# BBB_Cape_template.net
KiCad netlist of a schematic drawn in Altium Designer
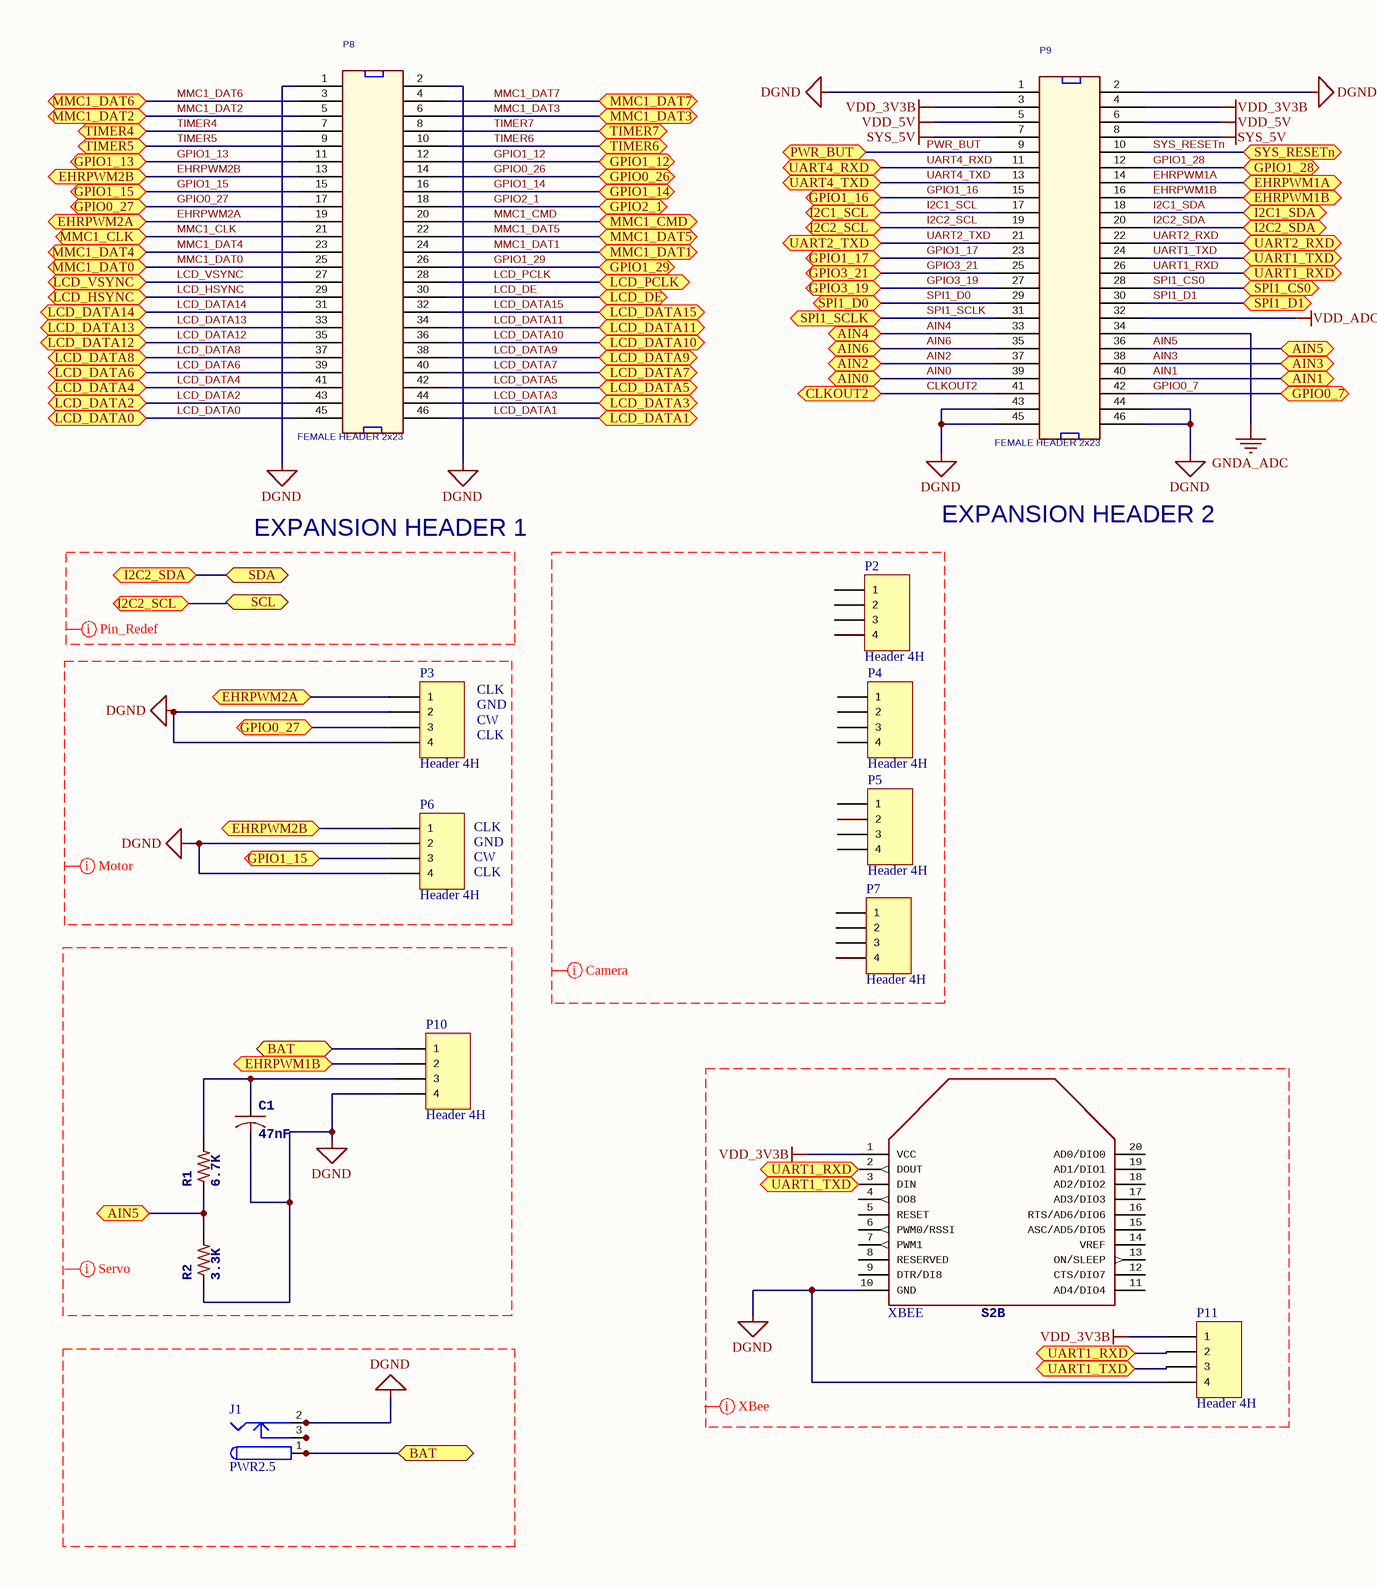
[diagram p0: BBB_Cape_template.SchDoc, left]
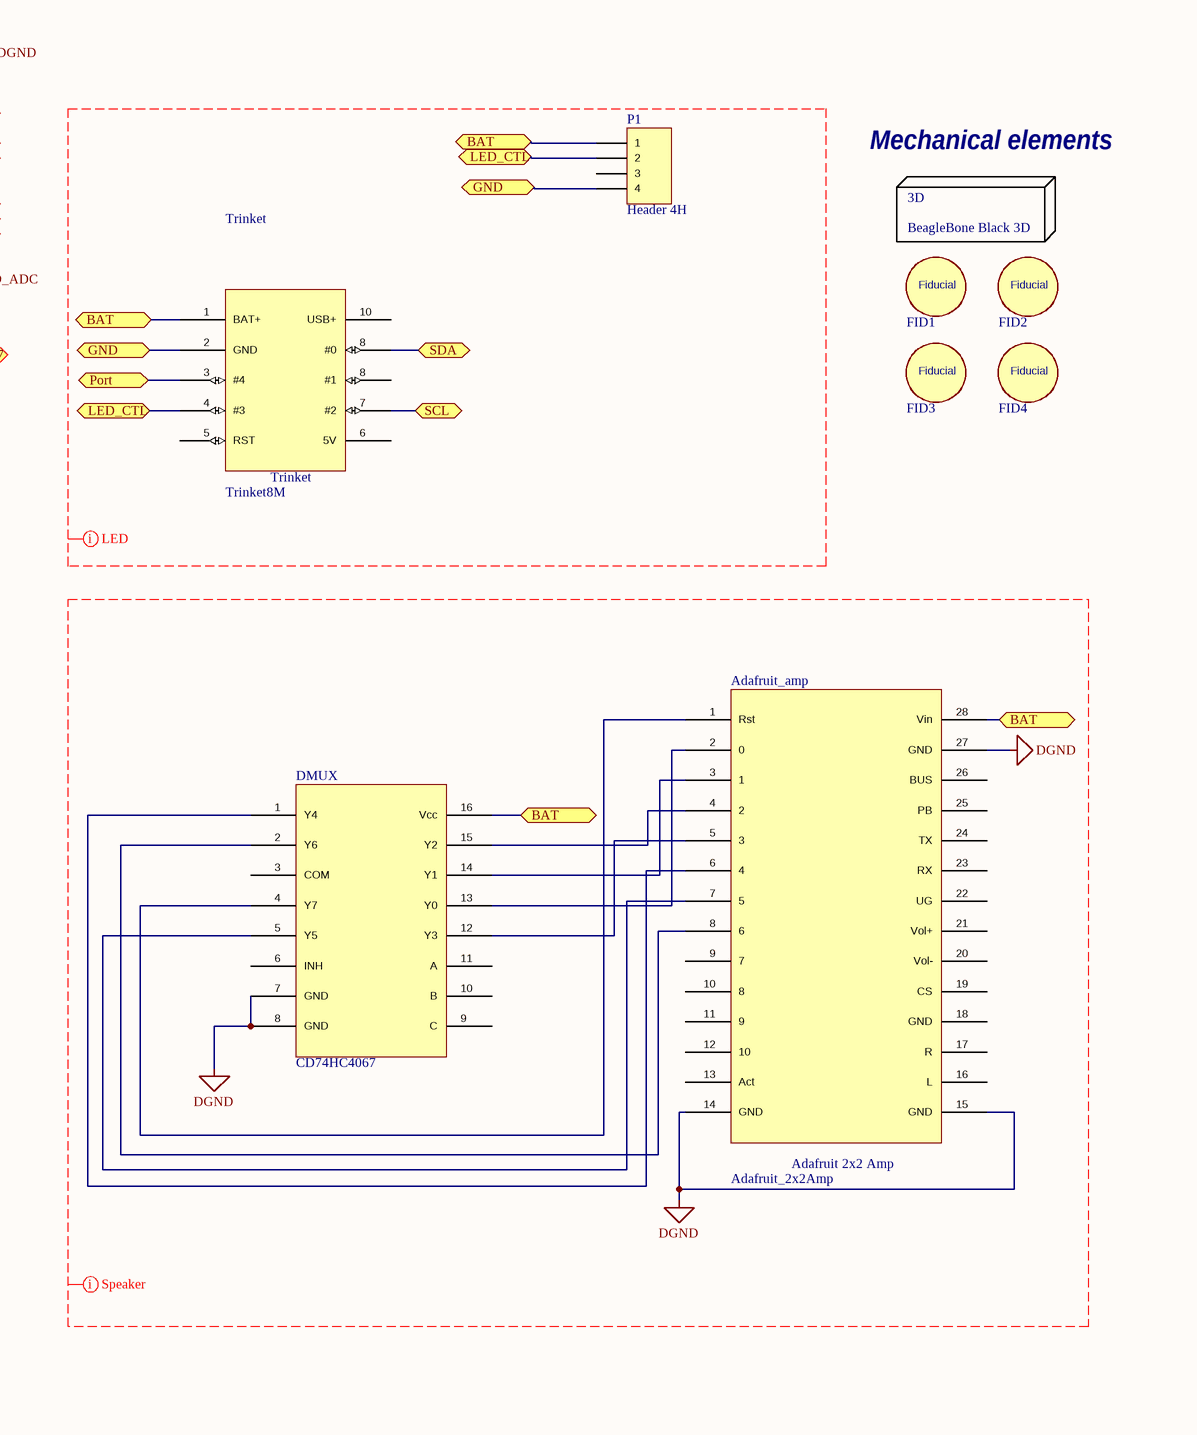
[diagram p1: BBB_Cape_template.SchDoc, right]

(export (version "E")
  (design (tool "Eeschema 10.0.6"))
  (components
    (comp (ref "3D") (value "BeagleBone Black 3D") (libsource (lib "Stamp") (part "BeagleBone Black 3D")))
    (comp (ref "Adafruit_amp")
      (value "Adafruit_2x2Amp")
      (footprint "adafruit_2x2w amp")
      (libsource (lib "KLibrary") (part "Adafruit_2x2Amp"))
    )
    (comp (ref "C1") (value "47nF") (footprint "C0805") (libsource (lib "adafruit") (part "C-USC0805")))
    (comp (ref "DMUX")
      (value "CD74HC4067")
      (footprint "so16")
      (libsource (lib "KLibrary") (part "CD74HC4067"))
    )
    (comp (ref "FID1")
      (value "MECH-Fiducial")
      (footprint "S_Fiducial")
      (description "Fiducial")
      (libsource (lib "Stamp") (part "MECH-Fiducial"))
    )
    (comp (ref "FID2")
      (value "MECH-Fiducial")
      (footprint "S_Fiducial")
      (description "Fiducial")
      (libsource (lib "Stamp") (part "MECH-Fiducial"))
    )
    (comp (ref "FID3")
      (value "MECH-Fiducial")
      (footprint "S_Fiducial")
      (description "Fiducial")
      (libsource (lib "Stamp") (part "MECH-Fiducial"))
    )
    (comp (ref "FID4")
      (value "MECH-Fiducial")
      (footprint "S_Fiducial")
      (description "Fiducial")
      (libsource (lib "Stamp") (part "MECH-Fiducial"))
    )
    (comp (ref "J1")
      (value "PWR2.5")
      (footprint "KLD-0202")
      (description "Low Voltage Power Supply Connector")
      (fields (field (name "PUBLISHER") "Altium Limited"))
      (libsource (lib "Miscellaneous Connectors") (part "PWR2.5"))
    )
    (comp (ref "P1")
      (value "Header 4H")
      (footprint "HDR1X4H")
      (description "Header, 4-Pin, Right Angle")
      (fields (field (name "PUBLISHER") "Altium Limited"))
      (libsource (lib "Miscellaneous Connectors") (part "Header 4H"))
    )
    (comp (ref "P2")
      (value "Header 4H")
      (footprint "HDR1X4H")
      (description "Header, 4-Pin, Right Angle")
      (fields (field (name "PUBLISHER") "Altium Limited"))
      (libsource (lib "Miscellaneous Connectors") (part "Header 4H"))
    )
    (comp (ref "P3")
      (value "Header 4H")
      (footprint "HDR1X4H")
      (description "Header, 4-Pin, Right Angle")
      (fields (field (name "PUBLISHER") "Altium Limited"))
      (libsource (lib "Miscellaneous Connectors") (part "Header 4H"))
    )
    (comp (ref "P4")
      (value "Header 4H")
      (footprint "HDR1X4H")
      (description "Header, 4-Pin, Right Angle")
      (fields (field (name "PUBLISHER") "Altium Limited"))
      (libsource (lib "Miscellaneous Connectors") (part "Header 4H"))
    )
    (comp (ref "P5")
      (value "Header 4H")
      (footprint "HDR1X4H")
      (description "Header, 4-Pin, Right Angle")
      (fields (field (name "PUBLISHER") "Altium Limited"))
      (libsource (lib "Miscellaneous Connectors") (part "Header 4H"))
    )
    (comp (ref "P6")
      (value "Header 4H")
      (footprint "HDR1X4H")
      (description "Header, 4-Pin, Right Angle")
      (fields (field (name "PUBLISHER") "Altium Limited"))
      (libsource (lib "Miscellaneous Connectors") (part "Header 4H"))
    )
    (comp (ref "P7")
      (value "Header 4H")
      (footprint "HDR1X4H")
      (description "Header, 4-Pin, Right Angle")
      (fields (field (name "PUBLISHER") "Altium Limited"))
      (libsource (lib "Miscellaneous Connectors") (part "Header 4H"))
    )
    (comp (ref "P8")
      (value "FEMALE HEADER 2x23")
      (description "CONN HEADER FMAL 46PS.1\" DL GOLD")
      (fields
        (field (name "MANUFACTURER") "Sullins Connector Solutions")
        (field (name "MANUFACTURER PART NUMBER") "PPPC232LFBN-RC")
      )
      (libsource (lib "BEAGLEBONEBLACK_REV A5B") (part "HDR_46_F_2_0.1_0.1"))
    )
    (comp (ref "P9")
      (value "FEMALE HEADER 2x23")
      (description "CONN HEADER FMAL 46PS.1\" DL GOLD")
      (fields
        (field (name "MANUFACTURER") "Sullins Connector Solutions")
        (field (name "MANUFACTURER PART NUMBER") "PPPC232LFBN-RC")
      )
      (libsource (lib "BEAGLEBONEBLACK_REV A5B") (part "HDR_46_F_2_0.1_0.1"))
    )
    (comp (ref "P10")
      (value "Header 4H")
      (footprint "HDR1X4H")
      (description "Header, 4-Pin, Right Angle")
      (fields (field (name "PUBLISHER") "Altium Limited"))
      (libsource (lib "Miscellaneous Connectors") (part "Header 4H"))
    )
    (comp (ref "P11")
      (value "Header 4H")
      (footprint "HDR1X4H")
      (description "Header, 4-Pin, Right Angle")
      (fields (field (name "PUBLISHER") "Altium Limited"))
      (libsource (lib "Miscellaneous Connectors") (part "Header 4H"))
    )
    (comp (ref "R1") (value "6.7K") (footprint "R0805") (libsource (lib "adafruit") (part "R-US_R0805")))
    (comp (ref "R2") (value "3.3K") (footprint "R0805") (libsource (lib "adafruit") (part "R-US_R0805")))
    (comp (ref "S2B") (value "XBEE") (footprint "XBEE") (libsource (lib "adafruit") (part "XBEE")))
    (comp (ref "Trinket")
      (value "Trinket8M")
      (footprint "trinket")
      (libsource (lib "KLibrary") (part "Trinket8M"))
    )
  )
  (nets
    (net (code "1") (name "/AIN0") (class "Default")
      (node (ref "P9") (pin "39") (pinfunction "20_39") (pintype "passive"))
    )
    (net (code "2") (name "/AIN1") (class "Default")
      (node (ref "P9") (pin "40") (pinfunction "45_40") (pintype "passive"))
    )
    (net (code "3") (name "/AIN2") (class "Default")
      (node (ref "P9") (pin "37") (pinfunction "19_37") (pintype "passive"))
    )
    (net (code "4") (name "/AIN3") (class "Default")
      (node (ref "P9") (pin "38") (pinfunction "44_38") (pintype "passive"))
    )
    (net (code "5") (name "/AIN4") (class "Default")
      (node (ref "P9") (pin "33") (pinfunction "17_33") (pintype "passive"))
    )
    (net (code "6") (name "/AIN5") (class "Default")
      (node (ref "P9") (pin "36") (pinfunction "43_36") (pintype "passive"))
      (node (ref "R1") (pin "1") (pinfunction "1_1") (pintype "passive"))
      (node (ref "R2") (pin "2") (pinfunction "2_2") (pintype "passive"))
    )
    (net (code "7") (name "/AIN6") (class "Default")
      (node (ref "P9") (pin "35") (pinfunction "18_35") (pintype "passive"))
    )
    (net (code "8") (name "/BAT") (class "Default")
      (node (ref "Adafruit_amp") (pin "28") (pinfunction "Vin_28") (pintype "passive"))
      (node (ref "DMUX") (pin "16") (pinfunction "Vcc_16") (pintype "passive"))
      (node (ref "J1") (pin "1") (pinfunction "1_1") (pintype "power_in"))
      (node (ref "J1") (pin "1A") (pinfunction "1A_1A") (pintype "power_in"))
      (node (ref "J1") (pin "1B") (pinfunction "1B_1B") (pintype "power_in"))
      (node (ref "P1") (pin "1") (pinfunction "1_1") (pintype "passive"))
      (node (ref "P10") (pin "1") (pinfunction "1_1") (pintype "passive"))
      (node (ref "Trinket") (pin "1") (pinfunction "BAT+_1") (pintype "power_in"))
    )
    (net (code "9") (name "/CLKOUT2") (class "Default")
      (node (ref "P9") (pin "41") (pinfunction "21_41") (pintype "passive"))
    )
    (net (code "10") (name "/EHRPWM1A") (class "Default")
      (node (ref "P9") (pin "14") (pinfunction "32_14") (pintype "passive"))
    )
    (net (code "11") (name "/EHRPWM1B") (class "Default")
      (node (ref "P10") (pin "2") (pinfunction "2_2") (pintype "passive"))
      (node (ref "P9") (pin "16") (pinfunction "33_16") (pintype "passive"))
    )
    (net (code "12") (name "/EHRPWM2A") (class "Default")
      (node (ref "P3") (pin "1") (pinfunction "1_1") (pintype "passive"))
      (node (ref "P8") (pin "19") (pinfunction "10_19") (pintype "passive"))
    )
    (net (code "13") (name "/EHRPWM2B") (class "Default")
      (node (ref "P6") (pin "1") (pinfunction "1_1") (pintype "passive"))
      (node (ref "P8") (pin "13") (pinfunction "7_13") (pintype "passive"))
    )
    (net (code "14") (name "/GND") (class "Default")
      (node (ref "P1") (pin "4") (pinfunction "4_4") (pintype "passive"))
      (node (ref "Trinket") (pin "2") (pinfunction "GND_2") (pintype "power_in"))
    )
    (net (code "15") (name "/GPIO0_7") (class "Default")
      (node (ref "P9") (pin "42") (pinfunction "46_42") (pintype "passive"))
    )
    (net (code "16") (name "/GPIO0_26") (class "Default")
      (node (ref "P8") (pin "14") (pinfunction "32_14") (pintype "passive"))
    )
    (net (code "17") (name "/GPIO0_27") (class "Default")
      (node (ref "P3") (pin "3") (pinfunction "3_3") (pintype "passive"))
      (node (ref "P8") (pin "17") (pinfunction "9_17") (pintype "passive"))
    )
    (net (code "18") (name "/GPIO1_12") (class "Default")
      (node (ref "P8") (pin "12") (pinfunction "31_12") (pintype "passive"))
    )
    (net (code "19") (name "/GPIO1_13") (class "Default")
      (node (ref "P8") (pin "11") (pinfunction "6_11") (pintype "passive"))
    )
    (net (code "20") (name "/GPIO1_14") (class "Default")
      (node (ref "P8") (pin "16") (pinfunction "33_16") (pintype "passive"))
    )
    (net (code "21") (name "/GPIO1_15") (class "Default")
      (node (ref "P6") (pin "3") (pinfunction "3_3") (pintype "passive"))
      (node (ref "P8") (pin "15") (pinfunction "8_15") (pintype "passive"))
    )
    (net (code "22") (name "/GPIO1_16") (class "Default")
      (node (ref "P9") (pin "15") (pinfunction "8_15") (pintype "passive"))
    )
    (net (code "23") (name "/GPIO1_17") (class "Default")
      (node (ref "P9") (pin "23") (pinfunction "12_23") (pintype "passive"))
    )
    (net (code "24") (name "/GPIO1_28") (class "Default")
      (node (ref "P9") (pin "12") (pinfunction "31_12") (pintype "passive"))
    )
    (net (code "25") (name "/GPIO1_29") (class "Default")
      (node (ref "P8") (pin "26") (pinfunction "38_26") (pintype "passive"))
    )
    (net (code "26") (name "/GPIO2_1") (class "Default")
      (node (ref "P8") (pin "18") (pinfunction "34_18") (pintype "passive"))
    )
    (net (code "27") (name "/GPIO3_19") (class "Default")
      (node (ref "P9") (pin "27") (pinfunction "14_27") (pintype "passive"))
    )
    (net (code "28") (name "/GPIO3_21") (class "Default")
      (node (ref "P9") (pin "25") (pinfunction "13_25") (pintype "passive"))
    )
    (net (code "29") (name "/I2C1_SCL") (class "Default")
      (node (ref "P9") (pin "17") (pinfunction "9_17") (pintype "passive"))
    )
    (net (code "30") (name "/I2C1_SDA") (class "Default")
      (node (ref "P9") (pin "18") (pinfunction "34_18") (pintype "passive"))
    )
    (net (code "31") (name "/I2C2_SCL") (class "Default")
      (node (ref "P9") (pin "19") (pinfunction "10_19") (pintype "passive"))
      (node (ref "Trinket") (pin "7") (pinfunction "#2_7") (pintype "bidirectional"))
    )
    (net (code "32") (name "/I2C2_SDA") (class "Default")
      (node (ref "P9") (pin "20") (pinfunction "35_20") (pintype "passive"))
      (node (ref "Trinket") (pin "8") (pinfunction "#0_8") (pintype "bidirectional"))
    )
    (net (code "33") (name "/LCD_DATA0") (class "Default")
      (node (ref "P8") (pin "45") (pinfunction "23_45") (pintype "passive"))
    )
    (net (code "34") (name "/LCD_DATA1") (class "Default")
      (node (ref "P8") (pin "46") (pinfunction "48_46") (pintype "passive"))
    )
    (net (code "35") (name "/LCD_DATA2") (class "Default")
      (node (ref "P8") (pin "43") (pinfunction "22_43") (pintype "passive"))
    )
    (net (code "36") (name "/LCD_DATA3") (class "Default")
      (node (ref "P8") (pin "44") (pinfunction "47_44") (pintype "passive"))
    )
    (net (code "37") (name "/LCD_DATA4") (class "Default")
      (node (ref "P8") (pin "41") (pinfunction "21_41") (pintype "passive"))
    )
    (net (code "38") (name "/LCD_DATA5") (class "Default")
      (node (ref "P8") (pin "42") (pinfunction "46_42") (pintype "passive"))
    )
    (net (code "39") (name "/LCD_DATA6") (class "Default")
      (node (ref "P8") (pin "39") (pinfunction "20_39") (pintype "passive"))
    )
    (net (code "40") (name "/LCD_DATA7") (class "Default")
      (node (ref "P8") (pin "40") (pinfunction "45_40") (pintype "passive"))
    )
    (net (code "41") (name "/LCD_DATA8") (class "Default")
      (node (ref "P8") (pin "37") (pinfunction "19_37") (pintype "passive"))
    )
    (net (code "42") (name "/LCD_DATA9") (class "Default")
      (node (ref "P8") (pin "38") (pinfunction "44_38") (pintype "passive"))
    )
    (net (code "43") (name "/LCD_DATA10") (class "Default")
      (node (ref "P8") (pin "36") (pinfunction "43_36") (pintype "passive"))
    )
    (net (code "44") (name "/LCD_DATA11") (class "Default")
      (node (ref "P8") (pin "34") (pinfunction "42_34") (pintype "passive"))
    )
    (net (code "45") (name "/LCD_DATA12") (class "Default")
      (node (ref "P8") (pin "35") (pinfunction "18_35") (pintype "passive"))
    )
    (net (code "46") (name "/LCD_DATA13") (class "Default")
      (node (ref "P8") (pin "33") (pinfunction "17_33") (pintype "passive"))
    )
    (net (code "47") (name "/LCD_DATA14") (class "Default")
      (node (ref "P8") (pin "31") (pinfunction "16_31") (pintype "passive"))
    )
    (net (code "48") (name "/LCD_DATA15") (class "Default")
      (node (ref "P8") (pin "32") (pinfunction "41_32") (pintype "passive"))
    )
    (net (code "49") (name "/LCD_DE") (class "Default")
      (node (ref "P8") (pin "30") (pinfunction "40_30") (pintype "passive"))
    )
    (net (code "50") (name "/LCD_HSYNC") (class "Default")
      (node (ref "P8") (pin "29") (pinfunction "15_29") (pintype "passive"))
    )
    (net (code "51") (name "/LCD_PCLK") (class "Default")
      (node (ref "P8") (pin "28") (pinfunction "39_28") (pintype "passive"))
    )
    (net (code "52") (name "/LCD_VSYNC") (class "Default")
      (node (ref "P8") (pin "27") (pinfunction "14_27") (pintype "passive"))
    )
    (net (code "53") (name "/LED_CTL") (class "Default")
      (node (ref "P1") (pin "2") (pinfunction "2_2") (pintype "passive"))
      (node (ref "Trinket") (pin "4") (pinfunction "#3_4") (pintype "bidirectional"))
    )
    (net (code "54") (name "/MMC1_CLK") (class "Default")
      (node (ref "P8") (pin "21") (pinfunction "11_21") (pintype "passive"))
    )
    (net (code "55") (name "/MMC1_CMD") (class "Default")
      (node (ref "P8") (pin "20") (pinfunction "35_20") (pintype "passive"))
    )
    (net (code "56") (name "/MMC1_DAT0") (class "Default")
      (node (ref "P8") (pin "25") (pinfunction "13_25") (pintype "passive"))
    )
    (net (code "57") (name "/MMC1_DAT1") (class "Default")
      (node (ref "P8") (pin "24") (pinfunction "37_24") (pintype "passive"))
    )
    (net (code "58") (name "/MMC1_DAT2") (class "Default")
      (node (ref "P8") (pin "5") (pinfunction "3_5") (pintype "passive"))
    )
    (net (code "59") (name "/MMC1_DAT3") (class "Default")
      (node (ref "P8") (pin "6") (pinfunction "28_6") (pintype "passive"))
    )
    (net (code "60") (name "/MMC1_DAT4") (class "Default")
      (node (ref "P8") (pin "23") (pinfunction "12_23") (pintype "passive"))
    )
    (net (code "61") (name "/MMC1_DAT5") (class "Default")
      (node (ref "P8") (pin "22") (pinfunction "36_22") (pintype "passive"))
    )
    (net (code "62") (name "/MMC1_DAT6") (class "Default")
      (node (ref "P8") (pin "3") (pinfunction "2_3") (pintype "passive"))
    )
    (net (code "63") (name "/MMC1_DAT7") (class "Default")
      (node (ref "P8") (pin "4") (pinfunction "27_4") (pintype "passive"))
    )
    (net (code "64") (name "/PWR_BUT") (class "Default")
      (node (ref "P9") (pin "9") (pinfunction "5_9") (pintype "passive"))
    )
    (net (code "65") (name "/Port") (class "Default")
      (node (ref "Trinket") (pin "3") (pinfunction "#4_3") (pintype "bidirectional"))
    )
    (net (code "66") (name "/SPI1_CS0") (class "Default")
      (node (ref "P9") (pin "28") (pinfunction "39_28") (pintype "passive"))
    )
    (net (code "67") (name "/SPI1_D0") (class "Default")
      (node (ref "P9") (pin "29") (pinfunction "15_29") (pintype "passive"))
    )
    (net (code "68") (name "/SPI1_D1") (class "Default")
      (node (ref "P9") (pin "30") (pinfunction "40_30") (pintype "passive"))
    )
    (net (code "69") (name "/SPI1_SCLK") (class "Default")
      (node (ref "P9") (pin "31") (pinfunction "16_31") (pintype "passive"))
    )
    (net (code "70") (name "/SYS_RESETn") (class "Default")
      (node (ref "P9") (pin "10") (pinfunction "30_10") (pintype "passive"))
    )
    (net (code "71") (name "/TIMER4") (class "Default")
      (node (ref "P8") (pin "7") (pinfunction "4_7") (pintype "passive"))
    )
    (net (code "72") (name "/TIMER5") (class "Default")
      (node (ref "P8") (pin "9") (pinfunction "5_9") (pintype "passive"))
    )
    (net (code "73") (name "/TIMER6") (class "Default")
      (node (ref "P8") (pin "10") (pinfunction "30_10") (pintype "passive"))
    )
    (net (code "74") (name "/TIMER7") (class "Default")
      (node (ref "P8") (pin "8") (pinfunction "29_8") (pintype "passive"))
    )
    (net (code "75") (name "/UART1_RXD") (class "Default")
      (node (ref "P11") (pin "2") (pinfunction "2_2") (pintype "passive"))
      (node (ref "P9") (pin "26") (pinfunction "38_26") (pintype "passive"))
      (node (ref "S2B") (pin "2") (pinfunction "DOUT_2") (pintype "output"))
    )
    (net (code "76") (name "/UART1_TXD") (class "Default")
      (node (ref "P11") (pin "3") (pinfunction "3_3") (pintype "passive"))
      (node (ref "P9") (pin "24") (pinfunction "37_24") (pintype "passive"))
      (node (ref "S2B") (pin "3") (pinfunction "DIN_3") (pintype "passive"))
    )
    (net (code "77") (name "/UART2_RXD") (class "Default")
      (node (ref "P9") (pin "22") (pinfunction "36_22") (pintype "passive"))
    )
    (net (code "78") (name "/UART2_TXD") (class "Default")
      (node (ref "P9") (pin "21") (pinfunction "11_21") (pintype "passive"))
    )
    (net (code "79") (name "/UART4_RXD") (class "Default")
      (node (ref "P9") (pin "11") (pinfunction "6_11") (pintype "passive"))
    )
    (net (code "80") (name "/UART4_TXD") (class "Default")
      (node (ref "P9") (pin "13") (pinfunction "7_13") (pintype "passive"))
    )
    (net (code "81") (name "DGND") (class "Default")
      (node (ref "Adafruit_amp") (pin "14") (pinfunction "GND_14") (pintype "passive"))
      (node (ref "Adafruit_amp") (pin "15") (pinfunction "GND_15") (pintype "passive"))
      (node (ref "Adafruit_amp") (pin "27") (pinfunction "GND_27") (pintype "passive"))
      (node (ref "C1") (pin "2") (pinfunction "2_2") (pintype "passive"))
      (node (ref "DMUX") (pin "7") (pinfunction "GND_7") (pintype "passive"))
      (node (ref "DMUX") (pin "8") (pinfunction "GND_8") (pintype "passive"))
      (node (ref "J1") (pin "2") (pinfunction "2_2") (pintype "power_in"))
      (node (ref "J1") (pin "2A") (pinfunction "2A_2A") (pintype "power_in"))
      (node (ref "J1") (pin "2B") (pinfunction "2B_2B") (pintype "power_in"))
      (node (ref "P10") (pin "4") (pinfunction "4_4") (pintype "passive"))
      (node (ref "P11") (pin "4") (pinfunction "4_4") (pintype "passive"))
      (node (ref "P3") (pin "2") (pinfunction "2_2") (pintype "passive"))
      (node (ref "P3") (pin "4") (pinfunction "4_4") (pintype "passive"))
      (node (ref "P6") (pin "2") (pinfunction "2_2") (pintype "passive"))
      (node (ref "P6") (pin "4") (pinfunction "4_4") (pintype "passive"))
      (node (ref "P8") (pin "1") (pinfunction "1_1") (pintype "passive"))
      (node (ref "P8") (pin "2") (pinfunction "26_2") (pintype "passive"))
      (node (ref "P9") (pin "1") (pinfunction "1_1") (pintype "passive"))
      (node (ref "P9") (pin "2") (pinfunction "26_2") (pintype "passive"))
      (node (ref "P9") (pin "43") (pinfunction "22_43") (pintype "passive"))
      (node (ref "P9") (pin "44") (pinfunction "47_44") (pintype "passive"))
      (node (ref "P9") (pin "45") (pinfunction "23_45") (pintype "passive"))
      (node (ref "P9") (pin "46") (pinfunction "48_46") (pintype "passive"))
      (node (ref "R2") (pin "1") (pinfunction "1_1") (pintype "passive"))
      (node (ref "S2B") (pin "10") (pinfunction "GND_10") (pintype "open_emitter"))
    )
    (net (code "82") (name "GNDA_ADC") (class "Default")
      (node (ref "P9") (pin "34") (pinfunction "42_34") (pintype "passive"))
    )
    (net (code "83") (name "Net-(Adafruit_amp-0)") (class "Default")
      (node (ref "Adafruit_amp") (pin "2") (pinfunction "0_2") (pintype "tri_state"))
      (node (ref "DMUX") (pin "13") (pinfunction "Y0_13") (pintype "passive"))
    )
    (net (code "84") (name "Net-(Adafruit_amp-1)") (class "Default")
      (node (ref "Adafruit_amp") (pin "3") (pinfunction "1_3") (pintype "tri_state"))
      (node (ref "DMUX") (pin "14") (pinfunction "Y1_14") (pintype "passive"))
    )
    (net (code "85") (name "Net-(Adafruit_amp-2)") (class "Default")
      (node (ref "Adafruit_amp") (pin "4") (pinfunction "2_4") (pintype "tri_state"))
      (node (ref "DMUX") (pin "15") (pinfunction "Y2_15") (pintype "passive"))
    )
    (net (code "86") (name "Net-(Adafruit_amp-3)") (class "Default")
      (node (ref "Adafruit_amp") (pin "5") (pinfunction "3_5") (pintype "passive"))
      (node (ref "DMUX") (pin "12") (pinfunction "Y3_12") (pintype "passive"))
    )
    (net (code "87") (name "Net-(Adafruit_amp-4)") (class "Default")
      (node (ref "Adafruit_amp") (pin "6") (pinfunction "4_6") (pintype "passive"))
      (node (ref "DMUX") (pin "1") (pinfunction "Y4_1") (pintype "passive"))
    )
    (net (code "88") (name "Net-(Adafruit_amp-5)") (class "Default")
      (node (ref "Adafruit_amp") (pin "7") (pinfunction "5_7") (pintype "passive"))
      (node (ref "DMUX") (pin "5") (pinfunction "Y5_5") (pintype "passive"))
    )
    (net (code "89") (name "Net-(Adafruit_amp-6)") (class "Default")
      (node (ref "Adafruit_amp") (pin "8") (pinfunction "6_8") (pintype "passive"))
      (node (ref "DMUX") (pin "2") (pinfunction "Y6_2") (pintype "passive"))
    )
    (net (code "90") (name "Net-(Adafruit_amp-Rst)") (class "Default")
      (node (ref "Adafruit_amp") (pin "1") (pinfunction "Rst_1") (pintype "passive"))
      (node (ref "DMUX") (pin "4") (pinfunction "Y7_4") (pintype "passive"))
    )
    (net (code "91") (name "Net-(C1-Pad1)") (class "Default")
      (node (ref "C1") (pin "1") (pinfunction "1_1") (pintype "passive"))
      (node (ref "P10") (pin "3") (pinfunction "3_3") (pintype "passive"))
      (node (ref "R1") (pin "2") (pinfunction "2_2") (pintype "passive"))
    )
    (net (code "92") (name "Net-(J1-Pad3)") (class "Default")
      (node (ref "J1") (pin "3") (pinfunction "3_3") (pintype "power_in"))
      (node (ref "J1") (pin "3A") (pinfunction "3A_3A") (pintype "power_in"))
      (node (ref "J1") (pin "3B") (pinfunction "3B_3B") (pintype "power_in"))
    )
    (net (code "93") (name "SYS_5V") (class "Default")
      (node (ref "P9") (pin "7") (pinfunction "4_7") (pintype "passive"))
      (node (ref "P9") (pin "8") (pinfunction "29_8") (pintype "passive"))
    )
    (net (code "94") (name "VDD_3V3B") (class "Default")
      (node (ref "P11") (pin "1") (pinfunction "1_1") (pintype "passive"))
      (node (ref "P9") (pin "3") (pinfunction "2_3") (pintype "passive"))
      (node (ref "P9") (pin "4") (pinfunction "27_4") (pintype "passive"))
      (node (ref "S2B") (pin "1") (pinfunction "VCC_1") (pintype "open_emitter"))
    )
    (net (code "95") (name "VDD_5V") (class "Default")
      (node (ref "P9") (pin "5") (pinfunction "3_5") (pintype "passive"))
      (node (ref "P9") (pin "6") (pinfunction "28_6") (pintype "passive"))
    )
    (net (code "96") (name "VDD_ADC") (class "Default")
      (node (ref "P9") (pin "32") (pinfunction "41_32") (pintype "passive"))
    )
    (net (code "97") (name "unconnected-(Adafruit_amp-7-Pad9)") (class "Default")
      (node (ref "Adafruit_amp") (pin "9") (pinfunction "7_9") (pintype "passive"))
    )
    (net (code "98") (name "unconnected-(Adafruit_amp-8-Pad10)") (class "Default")
      (node (ref "Adafruit_amp") (pin "10") (pinfunction "8_10") (pintype "passive"))
    )
    (net (code "99") (name "unconnected-(Adafruit_amp-9-Pad11)") (class "Default")
      (node (ref "Adafruit_amp") (pin "11") (pinfunction "9_11") (pintype "passive"))
    )
    (net (code "100") (name "unconnected-(Adafruit_amp-10-Pad12)") (class "Default")
      (node (ref "Adafruit_amp") (pin "12") (pinfunction "10_12") (pintype "passive"))
    )
    (net (code "101") (name "unconnected-(Adafruit_amp-Act-Pad13)") (class "Default")
      (node (ref "Adafruit_amp") (pin "13") (pinfunction "Act_13") (pintype "passive"))
    )
    (net (code "102") (name "unconnected-(Adafruit_amp-BUS-Pad26)") (class "Default")
      (node (ref "Adafruit_amp") (pin "26") (pinfunction "BUS_26") (pintype "passive"))
    )
    (net (code "103") (name "unconnected-(Adafruit_amp-CS-Pad19)") (class "Default")
      (node (ref "Adafruit_amp") (pin "19") (pinfunction "CS_19") (pintype "passive"))
    )
    (net (code "104") (name "unconnected-(Adafruit_amp-GND-Pad18)") (class "Default")
      (node (ref "Adafruit_amp") (pin "18") (pinfunction "GND_18") (pintype "passive"))
    )
    (net (code "105") (name "unconnected-(Adafruit_amp-L-Pad16)") (class "Default")
      (node (ref "Adafruit_amp") (pin "16") (pinfunction "L_16") (pintype "passive"))
    )
    (net (code "106") (name "unconnected-(Adafruit_amp-PB-Pad25)") (class "Default")
      (node (ref "Adafruit_amp") (pin "25") (pinfunction "PB_25") (pintype "passive"))
    )
    (net (code "107") (name "unconnected-(Adafruit_amp-R-Pad17)") (class "Default")
      (node (ref "Adafruit_amp") (pin "17") (pinfunction "R_17") (pintype "passive"))
    )
    (net (code "108") (name "unconnected-(Adafruit_amp-RX-Pad23)") (class "Default")
      (node (ref "Adafruit_amp") (pin "23") (pinfunction "RX_23") (pintype "passive"))
    )
    (net (code "109") (name "unconnected-(Adafruit_amp-TX-Pad24)") (class "Default")
      (node (ref "Adafruit_amp") (pin "24") (pinfunction "TX_24") (pintype "passive"))
    )
    (net (code "110") (name "unconnected-(Adafruit_amp-UG-Pad22)") (class "Default")
      (node (ref "Adafruit_amp") (pin "22") (pinfunction "UG_22") (pintype "passive"))
    )
    (net (code "111") (name "unconnected-(Adafruit_amp-Vol+-Pad21)") (class "Default")
      (node (ref "Adafruit_amp") (pin "21") (pinfunction "Vol+_21") (pintype "passive"))
    )
    (net (code "112") (name "unconnected-(Adafruit_amp-Vol--Pad20)") (class "Default")
      (node (ref "Adafruit_amp") (pin "20") (pinfunction "Vol-_20") (pintype "passive"))
    )
    (net (code "113") (name "unconnected-(DMUX-A-Pad11)") (class "Default")
      (node (ref "DMUX") (pin "11") (pinfunction "A_11") (pintype "passive"))
    )
    (net (code "114") (name "unconnected-(DMUX-B-Pad10)") (class "Default")
      (node (ref "DMUX") (pin "10") (pinfunction "B_10") (pintype "passive"))
    )
    (net (code "115") (name "unconnected-(DMUX-C-Pad9)") (class "Default")
      (node (ref "DMUX") (pin "9") (pinfunction "C_9") (pintype "passive"))
    )
    (net (code "116") (name "unconnected-(DMUX-COM-Pad3)") (class "Default")
      (node (ref "DMUX") (pin "3") (pinfunction "COM_3") (pintype "passive"))
    )
    (net (code "117") (name "unconnected-(DMUX-INH-Pad6)") (class "Default")
      (node (ref "DMUX") (pin "6") (pinfunction "INH_6") (pintype "passive"))
    )
    (net (code "118") (name "unconnected-(P1-Pad3)") (class "Default")
      (node (ref "P1") (pin "3") (pinfunction "3_3") (pintype "passive"))
    )
    (net (code "119") (name "unconnected-(P2-Pad1)") (class "Default")
      (node (ref "P2") (pin "1") (pinfunction "1_1") (pintype "passive"))
    )
    (net (code "120") (name "unconnected-(P2-Pad2)") (class "Default")
      (node (ref "P2") (pin "2") (pinfunction "2_2") (pintype "passive"))
    )
    (net (code "121") (name "unconnected-(P2-Pad3)") (class "Default")
      (node (ref "P2") (pin "3") (pinfunction "3_3") (pintype "passive"))
    )
    (net (code "122") (name "unconnected-(P2-Pad4)") (class "Default")
      (node (ref "P2") (pin "4") (pinfunction "4_4") (pintype "passive"))
    )
    (net (code "123") (name "unconnected-(P4-Pad1)") (class "Default")
      (node (ref "P4") (pin "1") (pinfunction "1_1") (pintype "passive"))
    )
    (net (code "124") (name "unconnected-(P4-Pad2)") (class "Default")
      (node (ref "P4") (pin "2") (pinfunction "2_2") (pintype "passive"))
    )
    (net (code "125") (name "unconnected-(P4-Pad3)") (class "Default")
      (node (ref "P4") (pin "3") (pinfunction "3_3") (pintype "passive"))
    )
    (net (code "126") (name "unconnected-(P4-Pad4)") (class "Default")
      (node (ref "P4") (pin "4") (pinfunction "4_4") (pintype "passive"))
    )
    (net (code "127") (name "unconnected-(P5-Pad1)") (class "Default")
      (node (ref "P5") (pin "1") (pinfunction "1_1") (pintype "passive"))
    )
    (net (code "128") (name "unconnected-(P5-Pad2)") (class "Default")
      (node (ref "P5") (pin "2") (pinfunction "2_2") (pintype "passive"))
    )
    (net (code "129") (name "unconnected-(P5-Pad3)") (class "Default")
      (node (ref "P5") (pin "3") (pinfunction "3_3") (pintype "passive"))
    )
    (net (code "130") (name "unconnected-(P5-Pad4)") (class "Default")
      (node (ref "P5") (pin "4") (pinfunction "4_4") (pintype "passive"))
    )
    (net (code "131") (name "unconnected-(P7-Pad1)") (class "Default")
      (node (ref "P7") (pin "1") (pinfunction "1_1") (pintype "passive"))
    )
    (net (code "132") (name "unconnected-(P7-Pad2)") (class "Default")
      (node (ref "P7") (pin "2") (pinfunction "2_2") (pintype "passive"))
    )
    (net (code "133") (name "unconnected-(P7-Pad3)") (class "Default")
      (node (ref "P7") (pin "3") (pinfunction "3_3") (pintype "passive"))
    )
    (net (code "134") (name "unconnected-(P7-Pad4)") (class "Default")
      (node (ref "P7") (pin "4") (pinfunction "4_4") (pintype "passive"))
    )
    (net (code "135") (name "unconnected-(S2B-AD0{slash}DIO0-Pad20)") (class "Default")
      (node (ref "S2B") (pin "20") (pinfunction "AD0/DIO0_20") (pintype "passive"))
    )
    (net (code "136") (name "unconnected-(S2B-AD1{slash}DIO1-Pad19)") (class "Default")
      (node (ref "S2B") (pin "19") (pinfunction "AD1/DIO1_19") (pintype "passive"))
    )
    (net (code "137") (name "unconnected-(S2B-AD2{slash}DIO2-Pad18)") (class "Default")
      (node (ref "S2B") (pin "18") (pinfunction "AD2/DIO2_18") (pintype "passive"))
    )
    (net (code "138") (name "unconnected-(S2B-AD3{slash}DIO3-Pad17)") (class "Default")
      (node (ref "S2B") (pin "17") (pinfunction "AD3/DIO3_17") (pintype "passive"))
    )
    (net (code "139") (name "unconnected-(S2B-AD4{slash}DIO4-Pad11)") (class "Default")
      (node (ref "S2B") (pin "11") (pinfunction "AD4/DIO4_11") (pintype "passive"))
    )
    (net (code "140") (name "unconnected-(S2B-ASC{slash}AD5{slash}DIO5-Pad15)") (class "Default")
      (node (ref "S2B") (pin "15") (pinfunction "ASC/AD5/DIO5_15") (pintype "passive"))
    )
    (net (code "141") (name "unconnected-(S2B-CTS{slash}DIO7-Pad12)") (class "Default")
      (node (ref "S2B") (pin "12") (pinfunction "CTS/DIO7_12") (pintype "passive"))
    )
    (net (code "142") (name "unconnected-(S2B-DO8-Pad4)") (class "Default")
      (node (ref "S2B") (pin "4") (pinfunction "DO8_4") (pintype "output"))
    )
    (net (code "143") (name "unconnected-(S2B-DTR{slash}DI8-Pad9)") (class "Default")
      (node (ref "S2B") (pin "9") (pinfunction "DTR/DI8_9") (pintype "passive"))
    )
    (net (code "144") (name "unconnected-(S2B-ON{slash}SLEEP-Pad13)") (class "Default")
      (node (ref "S2B") (pin "13") (pinfunction "ON/SLEEP_13") (pintype "output"))
    )
    (net (code "145") (name "unconnected-(S2B-PWM0{slash}RSSI-Pad6)") (class "Default")
      (node (ref "S2B") (pin "6") (pinfunction "PWM0/RSSI_6") (pintype "output"))
    )
    (net (code "146") (name "unconnected-(S2B-PWM1-Pad7)") (class "Default")
      (node (ref "S2B") (pin "7") (pinfunction "PWM1_7") (pintype "output"))
    )
    (net (code "147") (name "unconnected-(S2B-RESERVED-Pad8)") (class "Default")
      (node (ref "S2B") (pin "8") (pinfunction "RESERVED_8") (pintype "passive"))
    )
    (net (code "148") (name "unconnected-(S2B-RESET-Pad5)") (class "Default")
      (node (ref "S2B") (pin "5") (pinfunction "RESET_5") (pintype "passive"))
    )
    (net (code "149") (name "unconnected-(S2B-RTS{slash}AD6{slash}DIO6-Pad16)") (class "Default")
      (node (ref "S2B") (pin "16") (pinfunction "RTS/AD6/DIO6_16") (pintype "passive"))
    )
    (net (code "150") (name "unconnected-(S2B-VREF-Pad14)") (class "Default")
      (node (ref "S2B") (pin "14") (pinfunction "VREF_14") (pintype "passive"))
    )
    (net (code "151") (name "unconnected-(Trinket-#1-Pad8)") (class "Default")
      (node (ref "Trinket") (pin "8") (pinfunction "#1_8") (pintype "bidirectional"))
    )
    (net (code "152") (name "unconnected-(Trinket-5V-Pad6)") (class "Default")
      (node (ref "Trinket") (pin "6") (pinfunction "5V_6") (pintype "power_in"))
    )
    (net (code "153") (name "unconnected-(Trinket-RST-Pad5)") (class "Default")
      (node (ref "Trinket") (pin "5") (pinfunction "RST_5") (pintype "bidirectional"))
    )
    (net (code "154") (name "unconnected-(Trinket-USB+-Pad10)") (class "Default")
      (node (ref "Trinket") (pin "10") (pinfunction "USB+_10") (pintype "power_in"))
    )
  )
)
